# OpenEVSE_PLUS_v6_5_1.net
KiCad netlist of a schematic drawn in EAGLE
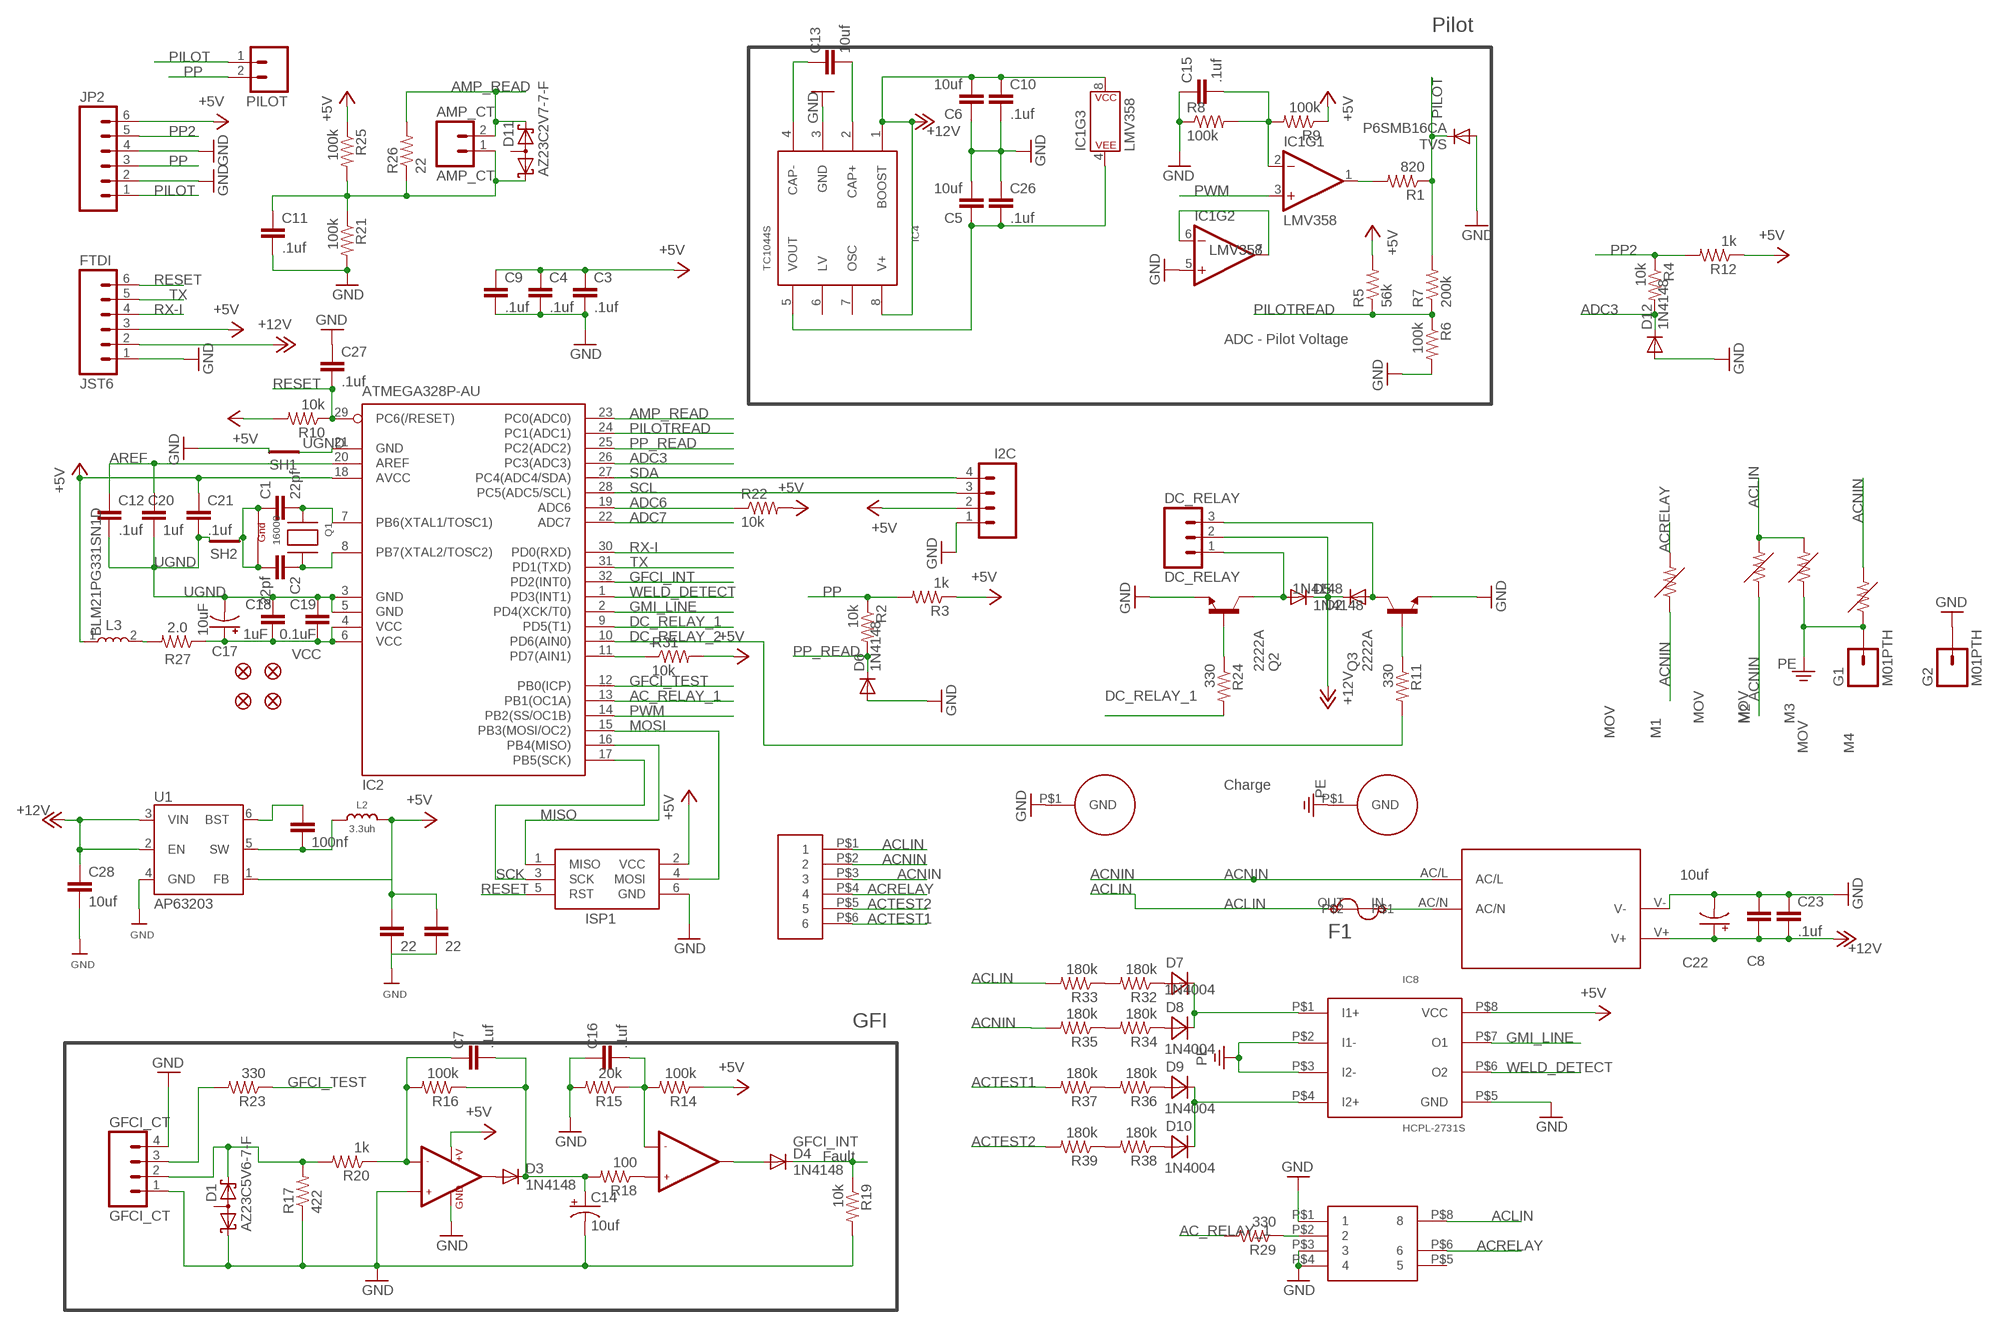
[diagram p0: schematic, sheet 1]

(export (version "E")
  (design (tool "Eeschema 10.0.6"))
  (components
    (comp (ref "AC")
      (value "JST-VH-6")
      (footprint "eagle-import:JST-VH-6")
      (libsource (lib "eagle-import") (part "JST-VH-6"))
    )
    (comp (ref "AMP_CT")
      (value "AMP_CT")
      (footprint "eagle-import:MOLEX_2")
      (libsource (lib "eagle-import") (part "MOLEX_2"))
    )
    (comp (ref "C1")
      (value "22pf")
      (footprint "eagle-import:0805")
      (libsource (lib "eagle-import") (part "CAP0805"))
    )
    (comp (ref "C2")
      (value "22pf")
      (footprint "eagle-import:0805")
      (libsource (lib "eagle-import") (part "CAP0805"))
    )
    (comp (ref "C3")
      (value ".1uf")
      (footprint "eagle-import:0805")
      (libsource (lib "eagle-import") (part "CAP0805"))
    )
    (comp (ref "C4")
      (value ".1uf")
      (footprint "eagle-import:0805")
      (libsource (lib "eagle-import") (part "CAP0805"))
    )
    (comp (ref "C5")
      (value "10uf")
      (footprint "eagle-import:0805")
      (libsource (lib "eagle-import") (part "CAP0805"))
    )
    (comp (ref "C6")
      (value "10uf")
      (footprint "eagle-import:0805")
      (libsource (lib "eagle-import") (part "CAP0805"))
    )
    (comp (ref "C7")
      (value ".1uf")
      (footprint "eagle-import:0805")
      (libsource (lib "eagle-import") (part "CAP0805"))
    )
    (comp (ref "C8")
      (value "1uf")
      (footprint "eagle-import:0805")
      (libsource (lib "eagle-import") (part "CAP0805"))
    )
    (comp (ref "C9")
      (value ".1uf")
      (footprint "eagle-import:0805")
      (libsource (lib "eagle-import") (part "CAP0805"))
    )
    (comp (ref "C10")
      (value ".1uf")
      (footprint "eagle-import:0805")
      (libsource (lib "eagle-import") (part "CAP0805"))
    )
    (comp (ref "C11")
      (value ".1uf")
      (footprint "eagle-import:0805")
      (libsource (lib "eagle-import") (part "CAP0805"))
    )
    (comp (ref "C12")
      (value ".1uf")
      (footprint "eagle-import:0805")
      (libsource (lib "eagle-import") (part "CAP0805"))
    )
    (comp (ref "C13")
      (value "10uf")
      (footprint "eagle-import:0805")
      (libsource (lib "eagle-import") (part "CAP0805"))
    )
    (comp (ref "C14")
      (value "10uf")
      (footprint "eagle-import:EIA3216")
      (libsource (lib "eagle-import") (part "CAP_POL1206"))
    )
    (comp (ref "C15")
      (value ".1uf")
      (footprint "eagle-import:0805")
      (libsource (lib "eagle-import") (part "CAP0805"))
    )
    (comp (ref "C16")
      (value ".1uf")
      (footprint "eagle-import:0805")
      (libsource (lib "eagle-import") (part "CAP0805"))
    )
    (comp (ref "C17")
      (value "10uF")
      (footprint "eagle-import:0603-POLAR")
      (libsource (lib "eagle-import") (part "10UF-POLAR-0603-6.3V-20%(TANT)"))
    )
    (comp (ref "C18")
      (value "1uF")
      (footprint "eagle-import:0805")
      (libsource (lib "eagle-import") (part "CAP0805"))
    )
    (comp (ref "C19")
      (value "0.1uF")
      (footprint "eagle-import:0805")
      (libsource (lib "eagle-import") (part "CAP0805"))
    )
    (comp (ref "C20")
      (value "1uf")
      (footprint "eagle-import:0805")
      (libsource (lib "eagle-import") (part "CAP0805"))
    )
    (comp (ref "C21")
      (value ".1uf")
      (footprint "eagle-import:0805")
      (libsource (lib "eagle-import") (part "CAP0805"))
    )
    (comp (ref "C22")
      (value "10uf")
      (footprint "eagle-import:EIA3216")
      (libsource (lib "eagle-import") (part "CAP_POL1206"))
    )
    (comp (ref "C23")
      (value ".1uf")
      (footprint "eagle-import:0805")
      (libsource (lib "eagle-import") (part "CAP0805"))
    )
    (comp (ref "C26")
      (value ".1uf")
      (footprint "eagle-import:0805")
      (libsource (lib "eagle-import") (part "CAP0805"))
    )
    (comp (ref "C27")
      (value ".1uf")
      (footprint "eagle-import:0805")
      (libsource (lib "eagle-import") (part "CAP0805"))
    )
    (comp (ref "C28")
      (value "10uf")
      (footprint "eagle-import:0805")
      (libsource (lib "eagle-import") (part "1.0UF-0805-25V-(+80/-20%)"))
    )
    (comp (ref "C29")
      (value "22")
      (footprint "eagle-import:0805")
      (libsource (lib "eagle-import") (part "1.0UF-0805-25V-(+80/-20%)"))
    )
    (comp (ref "C32")
      (value "100nf")
      (footprint "eagle-import:0805")
      (libsource (lib "eagle-import") (part "1.0UF-0805-25V-(+80/-20%)"))
    )
    (comp (ref "C33")
      (value "22")
      (footprint "eagle-import:0805")
      (libsource (lib "eagle-import") (part "1.0UF-0805-25V-(+80/-20%)"))
    )
    (comp (ref "D1")
      (value "AZ23C5V6-7-F")
      (footprint "eagle-import:SOT23")
      (libsource (lib "eagle-import") (part "BAS40-06"))
    )
    (comp (ref "D2")
      (value "1N4148")
      (footprint "eagle-import:SOD123")
      (libsource (lib "eagle-import") (part "DIODE-SOD123"))
    )
    (comp (ref "D3")
      (value "1N4148")
      (footprint "eagle-import:SOD123")
      (libsource (lib "eagle-import") (part "DIODE-SOD123"))
    )
    (comp (ref "D4")
      (value "1N4148")
      (footprint "eagle-import:SOD123")
      (libsource (lib "eagle-import") (part "DIODE-SOD123"))
    )
    (comp (ref "D5")
      (value "1N4148")
      (footprint "eagle-import:SOD123")
      (libsource (lib "eagle-import") (part "DIODE-SOD123"))
    )
    (comp (ref "D6")
      (value "1N4148")
      (footprint "eagle-import:SOD123")
      (libsource (lib "eagle-import") (part "DIODE-SOD123"))
    )
    (comp (ref "D7")
      (value "1N4004")
      (footprint "eagle-import:SMA")
      (libsource (lib "eagle-import") (part "MBRA340T3"))
    )
    (comp (ref "D8")
      (value "1N4004")
      (footprint "eagle-import:SMA")
      (libsource (lib "eagle-import") (part "MBRA340T3"))
    )
    (comp (ref "D9")
      (value "1N4004")
      (footprint "eagle-import:SMA")
      (libsource (lib "eagle-import") (part "MBRA340T3"))
    )
    (comp (ref "D10")
      (value "1N4004")
      (footprint "eagle-import:SMA")
      (libsource (lib "eagle-import") (part "MBRA340T3"))
    )
    (comp (ref "D11")
      (value "AZ23C2V7-7-F")
      (footprint "eagle-import:SOT23")
      (libsource (lib "eagle-import") (part "BAS40-06"))
    )
    (comp (ref "D12")
      (value "1N4148")
      (footprint "eagle-import:SOD123")
      (libsource (lib "eagle-import") (part "DIODE-SOD123"))
    )
    (comp (ref "DC_RELAY")
      (value "DC_RELAY")
      (footprint "eagle-import:MOLEX_3")
      (libsource (lib "eagle-import") (part "MOLEX_3"))
    )
    (comp (ref "F1")
      (value "BEL1.6AFUSE")
      (footprint "eagle-import:BELFUSE1A")
      (libsource (lib "eagle-import") (part "BEL1AFUSE"))
    )
    (comp (ref "FID1")
      (value "FIDUCIAL1X2.5")
      (footprint "eagle-import:FIDUCIAL-1X2.5")
      (libsource (lib "eagle-import") (part "FIDUCIAL1X2.5"))
    )
    (comp (ref "FID2")
      (value "FIDUCIAL1X2.5")
      (footprint "eagle-import:FIDUCIAL-1X2.5")
      (libsource (lib "eagle-import") (part "FIDUCIAL1X2.5"))
    )
    (comp (ref "FID3")
      (value "FIDUCIAL1X2.5")
      (footprint "eagle-import:FIDUCIAL-1X2.5")
      (libsource (lib "eagle-import") (part "FIDUCIAL1X2.5"))
    )
    (comp (ref "FID4")
      (value "FIDUCIAL1X2.5")
      (footprint "eagle-import:FIDUCIAL-1X2.5")
      (libsource (lib "eagle-import") (part "FIDUCIAL1X2.5"))
    )
    (comp (ref "FTDI")
      (value "JST6")
      (footprint "eagle-import:JST6")
      (libsource (lib "eagle-import") (part "JST6"))
    )
    (comp (ref "G1")
      (value "M01PTH")
      (footprint "eagle-import:1X01")
      (libsource (lib "eagle-import") (part "M01PTH"))
    )
    (comp (ref "G2")
      (value "M01PTH")
      (footprint "eagle-import:1X01")
      (libsource (lib "eagle-import") (part "M01PTH"))
    )
    (comp (ref "GFCI_CT")
      (value "GFCI_CT")
      (footprint "eagle-import:GFCI_4")
      (libsource (lib "eagle-import") (part "GFCI_4"))
    )
    (comp (ref "I2C")
      (value "M04JST-PTH-VERT")
      (footprint "eagle-import:JST-4-PTH-VERT")
      (libsource (lib "eagle-import") (part "M04JST-PTH-VERT"))
    )
    (comp (ref "IC1")
      (value "LMV358")
      (footprint "eagle-import:SO08")
      (libsource (lib "eagle-import") (part "LMV358SOIC"))
    )
    (comp (ref "IC2")
      (value "ATMEGA328P-AU")
      (footprint "eagle-import:TQFP32-08")
      (fields (field (name "MPN") "ATMEGA8-16AU"))
      (libsource (lib "eagle-import") (part "MEGA8-AI"))
    )
    (comp (ref "IC3")
      (value "LM358")
      (footprint "eagle-import:SO08")
      (libsource (lib "eagle-import") (part "LMV358"))
    )
    (comp (ref "IC4")
      (value "TC1044S")
      (footprint "eagle-import:SO-8")
      (libsource (lib "eagle-import") (part "TC1044S"))
    )
    (comp (ref "IC7")
      (value "AQH2223")
      (footprint "eagle-import:SIL8")
      (libsource (lib "eagle-import") (part "AQH2223"))
    )
    (comp (ref "IC8")
      (value "HCPL-2731S")
      (footprint "eagle-import:SIL8-2")
      (libsource (lib "eagle-import") (part "HCPL-2731S"))
    )
    (comp (ref "ISP1")
      (value "ISP1")
      (footprint "eagle-import:AVRISP")
      (libsource (lib "eagle-import") (part "AVRISP-6"))
    )
    (comp (ref "JP2")
      (value "M06POLAR_LOCK")
      (footprint "eagle-import:MOLEX-1X6_LOCK")
      (libsource (lib "eagle-import") (part "M06POLAR_LOCK"))
    )
    (comp (ref "L2")
      (value "3.3uh")
      (footprint "eagle-import:MICROBUILDER_INDUCTOR_5X5MM_NR5040_NOTHERMALS")
      (libsource (lib "eagle-import") (part "MICROBUILDER_INDUCTORNR5040"))
    )
    (comp (ref "L3")
      (value "BLM21PG331SN1D")
      (footprint "eagle-import:INDC2012X87")
      (fields (field (name "MF") "Murata"))
      (libsource (lib "eagle-import") (part "BLM21PG331SN1D"))
    )
    (comp (ref "M1")
      (value "MOV")
      (footprint "eagle-import:MOV")
      (libsource (lib "eagle-import") (part "MOV"))
    )
    (comp (ref "M2")
      (value "MOV")
      (footprint "eagle-import:MOV")
      (libsource (lib "eagle-import") (part "MOV"))
    )
    (comp (ref "M3")
      (value "MOV")
      (footprint "eagle-import:MOV")
      (libsource (lib "eagle-import") (part "MOV"))
    )
    (comp (ref "M4")
      (value "MOV")
      (footprint "eagle-import:MOV")
      (libsource (lib "eagle-import") (part "MOV"))
    )
    (comp (ref "PILOT")
      (value "M025MM")
      (footprint "eagle-import:SCREWTERMINAL-5MM-2")
      (libsource (lib "eagle-import") (part "M025MM"))
    )
    (comp (ref "PS1")
      (value "IRM-10-5")
      (footprint "eagle-import:IRM-10-5")
      (libsource (lib "eagle-import") (part "IRM-10-5"))
    )
    (comp (ref "Q1")
      (value "16000")
      (footprint "eagle-import:NX3225")
      (libsource (lib "eagle-import") (part "XTAL-4-3225"))
    )
    (comp (ref "Q2")
      (value "2222A")
      (footprint "eagle-import:SOT23")
      (libsource (lib "eagle-import") (part "BCX70SMD"))
    )
    (comp (ref "Q3")
      (value "2222A")
      (footprint "eagle-import:SOT23")
      (libsource (lib "eagle-import") (part "BCX70SMD"))
    )
    (comp (ref "R1")
      (value "820")
      (footprint "eagle-import:0805")
      (libsource (lib "eagle-import") (part "RESISTOR0805-RES"))
    )
    (comp (ref "R2")
      (value "10k")
      (footprint "eagle-import:0805")
      (libsource (lib "eagle-import") (part "RESISTOR0805-RES"))
    )
    (comp (ref "R3")
      (value "1k")
      (footprint "eagle-import:0805")
      (libsource (lib "eagle-import") (part "RESISTOR0805-RES"))
    )
    (comp (ref "R4")
      (value "10k")
      (footprint "eagle-import:0805")
      (libsource (lib "eagle-import") (part "RESISTOR0805-RES"))
    )
    (comp (ref "R5")
      (value "56k")
      (footprint "eagle-import:0805")
      (libsource (lib "eagle-import") (part "RESISTOR0805-RES"))
    )
    (comp (ref "R6")
      (value "100k")
      (footprint "eagle-import:0805")
      (libsource (lib "eagle-import") (part "RESISTOR0805-RES"))
    )
    (comp (ref "R7")
      (value "200k")
      (footprint "eagle-import:0805")
      (libsource (lib "eagle-import") (part "RESISTOR0805-RES"))
    )
    (comp (ref "R8")
      (value "100k")
      (footprint "eagle-import:0805")
      (libsource (lib "eagle-import") (part "RESISTOR0805-RES"))
    )
    (comp (ref "R9")
      (value "100k")
      (footprint "eagle-import:0805")
      (libsource (lib "eagle-import") (part "RESISTOR0805-RES"))
    )
    (comp (ref "R10")
      (value "10k")
      (footprint "eagle-import:0805")
      (libsource (lib "eagle-import") (part "RESISTOR0805-RES"))
    )
    (comp (ref "R11")
      (value "330")
      (footprint "eagle-import:0805")
      (libsource (lib "eagle-import") (part "RESISTOR0805-RES"))
    )
    (comp (ref "R12")
      (value "1k")
      (footprint "eagle-import:0805")
      (libsource (lib "eagle-import") (part "RESISTOR0805-RES"))
    )
    (comp (ref "R14")
      (value "100k")
      (footprint "eagle-import:0805")
      (libsource (lib "eagle-import") (part "RESISTOR0805-RES"))
    )
    (comp (ref "R15")
      (value "20k")
      (footprint "eagle-import:0805")
      (libsource (lib "eagle-import") (part "RESISTOR0805-RES"))
    )
    (comp (ref "R16")
      (value "100k")
      (footprint "eagle-import:0805")
      (libsource (lib "eagle-import") (part "RESISTOR0805-RES"))
    )
    (comp (ref "R17")
      (value "422")
      (footprint "eagle-import:0805")
      (libsource (lib "eagle-import") (part "RESISTOR0805-RES"))
    )
    (comp (ref "R18")
      (value "100")
      (footprint "eagle-import:0805")
      (libsource (lib "eagle-import") (part "RESISTOR0805-RES"))
    )
    (comp (ref "R19")
      (value "10k")
      (footprint "eagle-import:0805")
      (libsource (lib "eagle-import") (part "RESISTOR0805-RES"))
    )
    (comp (ref "R20")
      (value "1k")
      (footprint "eagle-import:0805")
      (libsource (lib "eagle-import") (part "RESISTOR0805-RES"))
    )
    (comp (ref "R21")
      (value "100k")
      (footprint "eagle-import:0805")
      (libsource (lib "eagle-import") (part "RESISTOR0805-RES"))
    )
    (comp (ref "R22")
      (value "10k")
      (footprint "eagle-import:0805")
      (libsource (lib "eagle-import") (part "RESISTOR0805-RES"))
    )
    (comp (ref "R23")
      (value "330")
      (footprint "eagle-import:0805")
      (libsource (lib "eagle-import") (part "RESISTOR0805-RES"))
    )
    (comp (ref "R24")
      (value "330")
      (footprint "eagle-import:0805")
      (libsource (lib "eagle-import") (part "RESISTOR0805-RES"))
    )
    (comp (ref "R25")
      (value "100k")
      (footprint "eagle-import:0805")
      (libsource (lib "eagle-import") (part "RESISTOR0805-RES"))
    )
    (comp (ref "R26")
      (value "22")
      (footprint "eagle-import:R1206")
      (libsource (lib "eagle-import") (part "R-US_R1206"))
    )
    (comp (ref "R27")
      (value "2.0")
      (footprint "eagle-import:0805")
      (libsource (lib "eagle-import") (part "RESISTOR0805-RES"))
    )
    (comp (ref "R29")
      (value "330")
      (footprint "eagle-import:0805")
      (libsource (lib "eagle-import") (part "RESISTOR0805-RES"))
    )
    (comp (ref "R31")
      (value "10k")
      (footprint "eagle-import:0805")
      (libsource (lib "eagle-import") (part "RESISTOR0805-RES"))
    )
    (comp (ref "R32")
      (value "180k")
      (footprint "eagle-import:1210")
      (libsource (lib "eagle-import") (part "0.1OHM-1/2W-1%(1210)"))
    )
    (comp (ref "R33")
      (value "180k")
      (footprint "eagle-import:1210")
      (libsource (lib "eagle-import") (part "0.1OHM-1/2W-1%(1210)"))
    )
    (comp (ref "R34")
      (value "180k")
      (footprint "eagle-import:1210")
      (libsource (lib "eagle-import") (part "0.1OHM-1/2W-1%(1210)"))
    )
    (comp (ref "R35")
      (value "180k")
      (footprint "eagle-import:1210")
      (libsource (lib "eagle-import") (part "0.1OHM-1/2W-1%(1210)"))
    )
    (comp (ref "R36")
      (value "180k")
      (footprint "eagle-import:1210")
      (libsource (lib "eagle-import") (part "0.1OHM-1/2W-1%(1210)"))
    )
    (comp (ref "R37")
      (value "180k")
      (footprint "eagle-import:1210")
      (libsource (lib "eagle-import") (part "0.1OHM-1/2W-1%(1210)"))
    )
    (comp (ref "R38")
      (value "180k")
      (footprint "eagle-import:1210")
      (libsource (lib "eagle-import") (part "0.1OHM-1/2W-1%(1210)"))
    )
    (comp (ref "R39")
      (value "180k")
      (footprint "eagle-import:1210")
      (libsource (lib "eagle-import") (part "0.1OHM-1/2W-1%(1210)"))
    )
    (comp (ref "SH1")
      (value "SHORT-HT5")
      (footprint "eagle-import:SHORT_TOP-50")
      (libsource (lib "eagle-import") (part "SHORT-HT5"))
    )
    (comp (ref "SH2")
      (value "SHORT-HT5")
      (footprint "eagle-import:SHORT_TOP-50")
      (libsource (lib "eagle-import") (part "SHORT-HT5"))
    )
    (comp (ref "TVS")
      (value "P6SMB16CA")
      (footprint "eagle-import:SMB")
      (libsource (lib "eagle-import") (part "DIODE-SMB"))
    )
    (comp (ref "U$3")
      (value "HOLE")
      (footprint "eagle-import:HOLE")
      (libsource (lib "eagle-import") (part "HOLE"))
    )
    (comp (ref "U$9")
      (value "HOLE")
      (footprint "eagle-import:HOLE")
      (libsource (lib "eagle-import") (part "HOLE"))
    )
    (comp (ref "U1")
      (value "AP63203")
      (footprint "eagle-import:SOT23-6")
      (libsource (lib "eagle-import") (part "AP63203"))
    )
  )
  (nets
    (net (code "1") (name "+5V") (class "Default")
      (node (ref "C21") (pin "1") (pinfunction "1_1") (pintype "passive"))
      (node (ref "C29") (pin "1") (pinfunction "1_1") (pintype "passive"))
      (node (ref "C3") (pin "1") (pinfunction "1_1") (pintype "passive"))
      (node (ref "C33") (pin "1") (pinfunction "1_1") (pintype "passive"))
      (node (ref "C4") (pin "1") (pinfunction "1_1") (pintype "passive"))
      (node (ref "C9") (pin "1") (pinfunction "1_1") (pintype "passive"))
      (node (ref "FTDI") (pin "3") (pinfunction "3_3") (pintype "passive"))
      (node (ref "I2C") (pin "2") (pinfunction "2_2") (pintype "passive"))
      (node (ref "IC2") (pin "18") (pinfunction "AVCC_18") (pintype "power_in"))
      (node (ref "IC3") (pin "8") (pinfunction "+V_8") (pintype "power_in"))
      (node (ref "IC8") (pin "P$8") (pinfunction "VCC_P$8") (pintype "bidirectional"))
      (node (ref "ISP1") (pin "2") (pinfunction "VCC_2") (pintype "power_in"))
      (node (ref "JP2") (pin "6") (pinfunction "6_6") (pintype "passive"))
      (node (ref "L2") (pin "P$2") (pinfunction "2_P$2") (pintype "passive"))
      (node (ref "L3") (pin "1") (pinfunction "1_1") (pintype "passive"))
      (node (ref "R10") (pin "2") (pinfunction "2_2") (pintype "passive"))
      (node (ref "R12") (pin "1") (pinfunction "1_1") (pintype "passive"))
      (node (ref "R14") (pin "1") (pinfunction "1_1") (pintype "passive"))
      (node (ref "R22") (pin "2") (pinfunction "2_2") (pintype "passive"))
      (node (ref "R25") (pin "1") (pinfunction "1_1") (pintype "passive"))
      (node (ref "R3") (pin "1") (pinfunction "1_1") (pintype "passive"))
      (node (ref "R31") (pin "2") (pinfunction "2_2") (pintype "passive"))
      (node (ref "R5") (pin "2") (pinfunction "2_2") (pintype "passive"))
      (node (ref "R9") (pin "1") (pinfunction "1_1") (pintype "passive"))
      (node (ref "U1") (pin "1") (pinfunction "FB_1") (pintype "bidirectional"))
    )
    (net (code "2") (name "+12V") (class "Default")
      (node (ref "C10") (pin "1") (pinfunction "1_1") (pintype "passive"))
      (node (ref "C22") (pin "A") (pinfunction "+_A") (pintype "passive"))
      (node (ref "C23") (pin "2") (pinfunction "2_2") (pintype "passive"))
      (node (ref "C28") (pin "1") (pinfunction "1_1") (pintype "passive"))
      (node (ref "C6") (pin "2") (pinfunction "2_2") (pintype "passive"))
      (node (ref "C8") (pin "1") (pinfunction "1_1") (pintype "passive"))
      (node (ref "D2") (pin "C") (pinfunction "C_C") (pintype "passive"))
      (node (ref "D5") (pin "C") (pinfunction "C_C") (pintype "passive"))
      (node (ref "DC_RELAY") (pin "2") (pinfunction "2_2") (pintype "passive"))
      (node (ref "FTDI") (pin "2") (pinfunction "2_2") (pintype "passive"))
      (node (ref "IC1") (pin "8") (pinfunction "P$V+_8") (pintype "bidirectional"))
      (node (ref "IC4") (pin "1") (pinfunction "BOOST_1") (pintype "bidirectional"))
      (node (ref "IC4") (pin "8") (pinfunction "V+_8") (pintype "bidirectional"))
      (node (ref "PS1") (pin "V+") (pinfunction "V+_V+") (pintype "bidirectional"))
      (node (ref "U1") (pin "2") (pinfunction "EN_2") (pintype "bidirectional"))
      (node (ref "U1") (pin "3") (pinfunction "VIN_3") (pintype "bidirectional"))
    )
    (net (code "3") (name "/ACLIN") (class "Default")
      (node (ref "AC") (pin "P$1") (pinfunction "1_P$1") (pintype "bidirectional"))
      (node (ref "F1") (pin "OUT") (pinfunction "P$1_OUT") (pintype "bidirectional"))
      (node (ref "IC7") (pin "P$8") (pinfunction "8_P$8") (pintype "bidirectional"))
      (node (ref "M2") (pin "P$2") (pinfunction "2_P$2") (pintype "passive"))
      (node (ref "M3") (pin "P$2") (pinfunction "2_P$2") (pintype "passive"))
      (node (ref "R33") (pin "2") (pinfunction "2_2") (pintype "passive"))
    )
    (net (code "4") (name "/ACNIN") (class "Default")
      (node (ref "AC") (pin "P$2") (pinfunction "2_P$2") (pintype "bidirectional"))
      (node (ref "AC") (pin "P$3") (pinfunction "3_P$3") (pintype "bidirectional"))
      (node (ref "M1") (pin "P$1") (pinfunction "1_P$1") (pintype "passive"))
      (node (ref "M2") (pin "P$1") (pinfunction "1_P$1") (pintype "passive"))
      (node (ref "M4") (pin "P$2") (pinfunction "2_P$2") (pintype "passive"))
      (node (ref "PS1") (pin "AC/L") (pinfunction "AC/L_AC/L") (pintype "bidirectional"))
      (node (ref "R35") (pin "2") (pinfunction "2_2") (pintype "passive"))
    )
    (net (code "5") (name "/ACRELAY") (class "Default")
      (node (ref "AC") (pin "P$4") (pinfunction "4_P$4") (pintype "bidirectional"))
      (node (ref "IC7") (pin "P$6") (pinfunction "6_P$6") (pintype "bidirectional"))
      (node (ref "M1") (pin "P$2") (pinfunction "2_P$2") (pintype "passive"))
    )
    (net (code "6") (name "/ACTEST1") (class "Default")
      (node (ref "AC") (pin "P$6") (pinfunction "6_P$6") (pintype "bidirectional"))
      (node (ref "R37") (pin "2") (pinfunction "2_2") (pintype "passive"))
    )
    (net (code "7") (name "/ACTEST2") (class "Default")
      (node (ref "AC") (pin "P$5") (pinfunction "5_P$5") (pintype "bidirectional"))
      (node (ref "R39") (pin "2") (pinfunction "2_2") (pintype "passive"))
    )
    (net (code "8") (name "/AC_RELAY_1") (class "Default")
      (node (ref "IC2") (pin "13") (pinfunction "PB1(OC1A)_13") (pintype "bidirectional"))
      (node (ref "R29") (pin "2") (pinfunction "2_2") (pintype "passive"))
    )
    (net (code "9") (name "/ADC3") (class "Default")
      (node (ref "D12") (pin "C") (pinfunction "C_C") (pintype "passive"))
      (node (ref "IC2") (pin "26") (pinfunction "PC3(ADC3)_26") (pintype "bidirectional"))
      (node (ref "R4") (pin "2") (pinfunction "2_2") (pintype "passive"))
    )
    (net (code "10") (name "/ADC6") (class "Default")
      (node (ref "IC2") (pin "19") (pinfunction "ADC6_19") (pintype "bidirectional"))
      (node (ref "R22") (pin "1") (pinfunction "1_1") (pintype "passive"))
    )
    (net (code "11") (name "/ADC7") (class "Default")
      (node (ref "IC2") (pin "22") (pinfunction "ADC7_22") (pintype "bidirectional"))
    )
    (net (code "12") (name "/AMP_READ") (class "Default")
      (node (ref "AMP_CT") (pin "2") (pinfunction "2_2") (pintype "passive"))
      (node (ref "D11") (pin "2") (pinfunction "K2_2") (pintype "passive"))
      (node (ref "IC2") (pin "23") (pinfunction "PC0(ADC0)_23") (pintype "bidirectional"))
      (node (ref "R26") (pin "2") (pinfunction "2_2") (pintype "passive"))
    )
    (net (code "13") (name "/AREF") (class "Default")
      (node (ref "C12") (pin "1") (pinfunction "1_1") (pintype "passive"))
      (node (ref "C20") (pin "1") (pinfunction "1_1") (pintype "passive"))
      (node (ref "IC2") (pin "20") (pinfunction "AREF_20") (pintype "passive"))
    )
    (net (code "14") (name "/DC_RELAY_1") (class "Default")
      (node (ref "IC2") (pin "9") (pinfunction "PD5(T1)_9") (pintype "bidirectional"))
      (node (ref "R24") (pin "2") (pinfunction "2_2") (pintype "passive"))
    )
    (net (code "15") (name "/DC_RELAY_2") (class "Default")
      (node (ref "IC2") (pin "10") (pinfunction "PD6(AIN0)_10") (pintype "bidirectional"))
      (node (ref "R11") (pin "2") (pinfunction "2_2") (pintype "passive"))
    )
    (net (code "16") (name "/GFCI_INT") (class "Default")
      (node (ref "D4") (pin "C") (pinfunction "C_C") (pintype "passive"))
      (node (ref "IC2") (pin "32") (pinfunction "PD2(INT0)_32") (pintype "bidirectional"))
      (node (ref "R19") (pin "1") (pinfunction "1_1") (pintype "passive"))
    )
    (net (code "17") (name "/GFCI_TEST") (class "Default")
      (node (ref "IC2") (pin "12") (pinfunction "PB0(ICP)_12") (pintype "bidirectional"))
      (node (ref "R23") (pin "1") (pinfunction "1_1") (pintype "passive"))
    )
    (net (code "18") (name "/GMI_LINE") (class "Default")
      (node (ref "IC2") (pin "2") (pinfunction "PD4(XCK/T0)_2") (pintype "bidirectional"))
      (node (ref "IC8") (pin "P$7") (pinfunction "O1_P$7") (pintype "bidirectional"))
    )
    (net (code "19") (name "/MISO") (class "Default")
      (node (ref "IC2") (pin "16") (pinfunction "PB4(MISO)_16") (pintype "bidirectional"))
      (node (ref "ISP1") (pin "1") (pinfunction "MISO_1") (pintype "input"))
    )
    (net (code "20") (name "/MOSI") (class "Default")
      (node (ref "IC2") (pin "15") (pinfunction "PB3(MOSI/OC2)_15") (pintype "bidirectional"))
      (node (ref "ISP1") (pin "4") (pinfunction "MOSI_4") (pintype "output"))
    )
    (net (code "21") (name "/PILOT") (class "Default")
      (node (ref "JP2") (pin "1") (pinfunction "1_1") (pintype "passive"))
      (node (ref "PILOT") (pin "1") (pinfunction "1_1") (pintype "passive"))
      (node (ref "R1") (pin "1") (pinfunction "1_1") (pintype "passive"))
      (node (ref "R7") (pin "2") (pinfunction "2_2") (pintype "passive"))
      (node (ref "TVS") (pin "C") (pinfunction "C_C") (pintype "passive"))
    )
    (net (code "22") (name "/PILOTREAD") (class "Default")
      (node (ref "IC2") (pin "24") (pinfunction "PC1(ADC1)_24") (pintype "bidirectional"))
      (node (ref "R5") (pin "1") (pinfunction "1_1") (pintype "passive"))
      (node (ref "R6") (pin "1") (pinfunction "1_1") (pintype "passive"))
      (node (ref "R7") (pin "1") (pinfunction "1_1") (pintype "passive"))
    )
    (net (code "23") (name "/PP") (class "Default")
      (node (ref "JP2") (pin "3") (pinfunction "3_3") (pintype "passive"))
      (node (ref "PILOT") (pin "2") (pinfunction "2_2") (pintype "passive"))
      (node (ref "R2") (pin "1") (pinfunction "1_1") (pintype "passive"))
      (node (ref "R3") (pin "2") (pinfunction "2_2") (pintype "passive"))
    )
    (net (code "24") (name "/PP2") (class "Default")
      (node (ref "JP2") (pin "5") (pinfunction "5_5") (pintype "passive"))
      (node (ref "R12") (pin "2") (pinfunction "2_2") (pintype "passive"))
      (node (ref "R4") (pin "1") (pinfunction "1_1") (pintype "passive"))
    )
    (net (code "25") (name "/PP_READ") (class "Default")
      (node (ref "D6") (pin "C") (pinfunction "C_C") (pintype "passive"))
      (node (ref "IC2") (pin "25") (pinfunction "PC2(ADC2)_25") (pintype "bidirectional"))
      (node (ref "R2") (pin "2") (pinfunction "2_2") (pintype "passive"))
    )
    (net (code "26") (name "/PWM") (class "Default")
      (node (ref "IC1") (pin "3") (pinfunction "+IN_3") (pintype "input"))
      (node (ref "IC2") (pin "14") (pinfunction "PB2(SS/OC1B)_14") (pintype "bidirectional"))
    )
    (net (code "27") (name "/RESET") (class "Default")
      (node (ref "C27") (pin "2") (pinfunction "2_2") (pintype "passive"))
      (node (ref "FTDI") (pin "6") (pinfunction "6_6") (pintype "passive"))
      (node (ref "IC2") (pin "29") (pinfunction "PC6(/RESET)_29") (pintype "bidirectional"))
      (node (ref "ISP1") (pin "5") (pinfunction "RST_5") (pintype "output"))
      (node (ref "R10") (pin "1") (pinfunction "1_1") (pintype "passive"))
    )
    (net (code "28") (name "/RX-I") (class "Default")
      (node (ref "FTDI") (pin "4") (pinfunction "4_4") (pintype "passive"))
      (node (ref "IC2") (pin "30") (pinfunction "PD0(RXD)_30") (pintype "bidirectional"))
    )
    (net (code "29") (name "/SCK") (class "Default")
      (node (ref "IC2") (pin "17") (pinfunction "PB5(SCK)_17") (pintype "bidirectional"))
      (node (ref "ISP1") (pin "3") (pinfunction "SCK_3") (pintype "output"))
    )
    (net (code "30") (name "/SCL") (class "Default")
      (node (ref "I2C") (pin "3") (pinfunction "3_3") (pintype "passive"))
      (node (ref "IC2") (pin "28") (pinfunction "PC5(ADC5/SCL)_28") (pintype "bidirectional"))
    )
    (net (code "31") (name "/SDA") (class "Default")
      (node (ref "I2C") (pin "4") (pinfunction "4_4") (pintype "passive"))
      (node (ref "IC2") (pin "27") (pinfunction "PC4(ADC4/SDA)_27") (pintype "bidirectional"))
    )
    (net (code "32") (name "/TX") (class "Default")
      (node (ref "FTDI") (pin "5") (pinfunction "5_5") (pintype "passive"))
      (node (ref "IC2") (pin "31") (pinfunction "PD1(TXD)_31") (pintype "bidirectional"))
    )
    (net (code "33") (name "/UGND") (class "Default")
      (node (ref "C12") (pin "2") (pinfunction "2_2") (pintype "passive"))
      (node (ref "C17") (pin "-") (pinfunction "-_-") (pintype "passive"))
      (node (ref "C18") (pin "1") (pinfunction "1_1") (pintype "passive"))
      (node (ref "C19") (pin "1") (pinfunction "1_1") (pintype "passive"))
      (node (ref "C20") (pin "2") (pinfunction "2_2") (pintype "passive"))
      (node (ref "C21") (pin "2") (pinfunction "2_2") (pintype "passive"))
      (node (ref "IC2") (pin "21") (pinfunction "GND_21") (pintype "power_in"))
      (node (ref "IC2") (pin "3") (pinfunction "GND_3") (pintype "power_in"))
      (node (ref "IC2") (pin "5") (pinfunction "GND_5") (pintype "power_in"))
      (node (ref "SH1") (pin "1") (pinfunction "P$1_1") (pintype "bidirectional"))
      (node (ref "SH2") (pin "2") (pinfunction "P$2_2") (pintype "bidirectional"))
    )
    (net (code "34") (name "/VCC") (class "Default")
      (node (ref "C17") (pin "+") (pinfunction "+_+") (pintype "passive"))
      (node (ref "C18") (pin "2") (pinfunction "2_2") (pintype "passive"))
      (node (ref "C19") (pin "2") (pinfunction "2_2") (pintype "passive"))
      (node (ref "IC2") (pin "4") (pinfunction "VCC_4") (pintype "power_in"))
      (node (ref "IC2") (pin "6") (pinfunction "VCC_6") (pintype "power_in"))
      (node (ref "R27") (pin "1") (pinfunction "1_1") (pintype "passive"))
    )
    (net (code "35") (name "/WELD_DETECT") (class "Default")
      (node (ref "IC2") (pin "1") (pinfunction "PD3(INT1)_1") (pintype "bidirectional"))
      (node (ref "IC8") (pin "P$6") (pinfunction "O2_P$6") (pintype "bidirectional"))
    )
    (net (code "36") (name "GND") (class "Default")
      (node (ref "C10") (pin "2") (pinfunction "2_2") (pintype "passive"))
      (node (ref "C11") (pin "2") (pinfunction "2_2") (pintype "passive"))
      (node (ref "C14") (pin "C") (pinfunction "-_C") (pintype "passive"))
      (node (ref "C15") (pin "1") (pinfunction "1_1") (pintype "passive"))
      (node (ref "C16") (pin "1") (pinfunction "1_1") (pintype "passive"))
      (node (ref "C22") (pin "C") (pinfunction "-_C") (pintype "passive"))
      (node (ref "C23") (pin "1") (pinfunction "1_1") (pintype "passive"))
      (node (ref "C26") (pin "1") (pinfunction "1_1") (pintype "passive"))
      (node (ref "C27") (pin "1") (pinfunction "1_1") (pintype "passive"))
      (node (ref "C28") (pin "2") (pinfunction "2_2") (pintype "passive"))
      (node (ref "C29") (pin "2") (pinfunction "2_2") (pintype "passive"))
      (node (ref "C3") (pin "2") (pinfunction "2_2") (pintype "passive"))
      (node (ref "C33") (pin "2") (pinfunction "2_2") (pintype "passive"))
      (node (ref "C4") (pin "2") (pinfunction "2_2") (pintype "passive"))
      (node (ref "C5") (pin "2") (pinfunction "2_2") (pintype "passive"))
      (node (ref "C6") (pin "1") (pinfunction "1_1") (pintype "passive"))
      (node (ref "C8") (pin "2") (pinfunction "2_2") (pintype "passive"))
      (node (ref "C9") (pin "2") (pinfunction "2_2") (pintype "passive"))
      (node (ref "D1") (pin "1") (pinfunction "K1_1") (pintype "passive"))
      (node (ref "D12") (pin "A") (pinfunction "A_A") (pintype "passive"))
      (node (ref "D6") (pin "A") (pinfunction "A_A") (pintype "passive"))
      (node (ref "FTDI") (pin "1") (pinfunction "1_1") (pintype "passive"))
      (node (ref "G2") (pin "1") (pinfunction "1_1") (pintype "passive"))
      (node (ref "GFCI_CT") (pin "1") (pinfunction "1_1") (pintype "passive"))
      (node (ref "GFCI_CT") (pin "4") (pinfunction "4_4") (pintype "passive"))
      (node (ref "I2C") (pin "1") (pinfunction "1_1") (pintype "passive"))
      (node (ref "IC1") (pin "5") (pinfunction "+IN_5") (pintype "input"))
      (node (ref "IC3") (pin "3") (pinfunction "+IN1_3") (pintype "input"))
      (node (ref "IC3") (pin "4") (pinfunction "GND_4") (pintype "power_in"))
      (node (ref "IC4") (pin "3") (pinfunction "GND_3") (pintype "bidirectional"))
      (node (ref "IC7") (pin "P$1") (pinfunction "1_P$1") (pintype "bidirectional"))
      (node (ref "IC7") (pin "P$3") (pinfunction "3_P$3") (pintype "bidirectional"))
      (node (ref "IC7") (pin "P$4") (pinfunction "4_P$4") (pintype "bidirectional"))
      (node (ref "IC8") (pin "P$5") (pinfunction "GND_P$5") (pintype "bidirectional"))
      (node (ref "ISP1") (pin "6") (pinfunction "GND_6") (pintype "power_in"))
      (node (ref "JP2") (pin "2") (pinfunction "2_2") (pintype "passive"))
      (node (ref "JP2") (pin "4") (pinfunction "4_4") (pintype "passive"))
      (node (ref "PS1") (pin "V-") (pinfunction "V-_V-") (pintype "bidirectional"))
      (node (ref "Q2") (pin "2") (pinfunction "E_2") (pintype "passive"))
      (node (ref "Q3") (pin "2") (pinfunction "E_2") (pintype "passive"))
      (node (ref "R15") (pin "2") (pinfunction "2_2") (pintype "passive"))
      (node (ref "R17") (pin "1") (pinfunction "1_1") (pintype "passive"))
      (node (ref "R19") (pin "2") (pinfunction "2_2") (pintype "passive"))
      (node (ref "R21") (pin "2") (pinfunction "2_2") (pintype "passive"))
      (node (ref "R6") (pin "2") (pinfunction "2_2") (pintype "passive"))
      (node (ref "R8") (pin "1") (pinfunction "1_1") (pintype "passive"))
      (node (ref "SH1") (pin "2") (pinfunction "P$2_2") (pintype "bidirectional"))
      (node (ref "TVS") (pin "A") (pinfunction "A_A") (pintype "passive"))
      (node (ref "U$9") (pin "P$1") (pinfunction "GND_P$1") (pintype "bidirectional"))
      (node (ref "U1") (pin "4") (pinfunction "GND_4") (pintype "bidirectional"))
    )
    (net (code "37") (name "Net-(C14-+)") (class "Default")
      (node (ref "C14") (pin "A") (pinfunction "+_A") (pintype "passive"))
      (node (ref "C7") (pin "2") (pinfunction "2_2") (pintype "passive"))
      (node (ref "D3") (pin "C") (pinfunction "C_C") (pintype "passive"))
      (node (ref "R16") (pin "1") (pinfunction "1_1") (pintype "passive"))
      (node (ref "R18") (pin "2") (pinfunction "2_2") (pintype "passive"))
    )
    (net (code "38") (name "Net-(D1-K2)") (class "Default")
      (node (ref "D1") (pin "2") (pinfunction "K2_2") (pintype "passive"))
      (node (ref "GFCI_CT") (pin "2") (pinfunction "2_2") (pintype "passive"))
      (node (ref "R17") (pin "2") (pinfunction "2_2") (pintype "passive"))
      (node (ref "R20") (pin "2") (pinfunction "2_2") (pintype "passive"))
    )
    (net (code "39") (name "Net-(D7-PadA)") (class "Default")
      (node (ref "D7") (pin "A") (pinfunction "A_A") (pintype "passive"))
      (node (ref "R32") (pin "1") (pinfunction "1_1") (pintype "passive"))
    )
    (net (code "40") (name "Net-(D8-PadA)") (class "Default")
      (node (ref "D8") (pin "A") (pinfunction "A_A") (pintype "passive"))
      (node (ref "R34") (pin "1") (pinfunction "1_1") (pintype "passive"))
    )
    (net (code "41") (name "Net-(D9-PadA)") (class "Default")
      (node (ref "D9") (pin "A") (pinfunction "A_A") (pintype "passive"))
      (node (ref "R36") (pin "1") (pinfunction "1_1") (pintype "passive"))
    )
    (net (code "42") (name "Net-(D10-PadA)") (class "Default")
      (node (ref "D10") (pin "A") (pinfunction "A_A") (pintype "passive"))
      (node (ref "R38") (pin "1") (pinfunction "1_1") (pintype "passive"))
    )
    (net (code "43") (name "Net-(D11-K1)") (class "Default")
      (node (ref "AMP_CT") (pin "1") (pinfunction "1_1") (pintype "passive"))
      (node (ref "C11") (pin "1") (pinfunction "1_1") (pintype "passive"))
      (node (ref "D11") (pin "1") (pinfunction "K1_1") (pintype "passive"))
      (node (ref "R21") (pin "1") (pinfunction "1_1") (pintype "passive"))
      (node (ref "R25") (pin "2") (pinfunction "2_2") (pintype "passive"))
      (node (ref "R26") (pin "1") (pinfunction "1_1") (pintype "passive"))
    )
    (net (code "44") (name "Net-(F1-P$2)") (class "Default")
      (node (ref "F1") (pin "IN") (pinfunction "P$2_IN") (pintype "bidirectional"))
      (node (ref "PS1") (pin "AC/N") (pinfunction "AC/N_AC/N") (pintype "bidirectional"))
    )
    (net (code "45") (name "Net-(GFCI_CT-Pad3)") (class "Default")
      (node (ref "GFCI_CT") (pin "3") (pinfunction "3_3") (pintype "passive"))
      (node (ref "R23") (pin "2") (pinfunction "2_2") (pintype "passive"))
    )
    (net (code "46") (name "Net-(IC1A--IN)") (class "Default")
      (node (ref "C15") (pin "2") (pinfunction "2_2") (pintype "passive"))
      (node (ref "IC1") (pin "2") (pinfunction "-IN_2") (pintype "input"))
      (node (ref "R8") (pin "2") (pinfunction "2_2") (pintype "passive"))
      (node (ref "R9") (pin "2") (pinfunction "2_2") (pintype "passive"))
    )
    (net (code "47") (name "Net-(IC1A-OUT)") (class "Default")
      (node (ref "IC1") (pin "1") (pinfunction "OUT_1") (pintype "output"))
      (node (ref "R1") (pin "2") (pinfunction "2_2") (pintype "passive"))
    )
    (net (code "48") (name "Net-(IC1B--IN)") (class "Default")
      (node (ref "IC1") (pin "6") (pinfunction "-IN_6") (pintype "input"))
      (node (ref "IC1") (pin "7") (pinfunction "OUT_7") (pintype "output"))
    )
    (net (code "49") (name "Net-(IC1C-P$V-)") (class "Default")
      (node (ref "C26") (pin "2") (pinfunction "2_2") (pintype "passive"))
      (node (ref "C5") (pin "1") (pinfunction "1_1") (pintype "passive"))
      (node (ref "IC1") (pin "4") (pinfunction "P$V-_4") (pintype "bidirectional"))
      (node (ref "IC4") (pin "5") (pinfunction "VOUT_5") (pintype "bidirectional"))
    )
    (net (code "50") (name "Net-(IC2-PB6(XTAL1{slash}TOSC1))") (class "Default")
      (node (ref "C1") (pin "2") (pinfunction "2_2") (pintype "passive"))
      (node (ref "IC2") (pin "7") (pinfunction "PB6(XTAL1/TOSC1)_7") (pintype "bidirectional"))
      (node (ref "Q1") (pin "2") (pinfunction "X1_2") (pintype "bidirectional"))
    )
    (net (code "51") (name "Net-(IC2-PB7(XTAL2{slash}TOSC2))") (class "Default")
      (node (ref "C2") (pin "1") (pinfunction "1_1") (pintype "passive"))
      (node (ref "IC2") (pin "8") (pinfunction "PB7(XTAL2/TOSC2)_8") (pintype "bidirectional"))
      (node (ref "Q1") (pin "4") (pinfunction "X2_4") (pintype "bidirectional"))
    )
    (net (code "52") (name "Net-(IC2-PD7(AIN1))") (class "Default")
      (node (ref "IC2") (pin "11") (pinfunction "PD7(AIN1)_11") (pintype "bidirectional"))
      (node (ref "R31") (pin "1") (pinfunction "1_1") (pintype "passive"))
    )
    (net (code "53") (name "Net-(IC3A--IN1)") (class "Default")
      (node (ref "C7") (pin "1") (pinfunction "1_1") (pintype "passive"))
      (node (ref "IC3") (pin "2") (pinfunction "-IN1_2") (pintype "input"))
      (node (ref "R16") (pin "2") (pinfunction "2_2") (pintype "passive"))
      (node (ref "R20") (pin "1") (pinfunction "1_1") (pintype "passive"))
    )
    (net (code "54") (name "Net-(IC3A-OUT1)") (class "Default")
      (node (ref "D3") (pin "A") (pinfunction "A_A") (pintype "passive"))
      (node (ref "IC3") (pin "1") (pinfunction "OUT1_1") (pintype "output"))
    )
    (net (code "55") (name "Net-(IC3B-+IN2)") (class "Default")
      (node (ref "IC3") (pin "5") (pinfunction "+IN2_5") (pintype "input"))
      (node (ref "R18") (pin "1") (pinfunction "1_1") (pintype "passive"))
    )
    (net (code "56") (name "Net-(IC3B--IN2)") (class "Default")
      (node (ref "C16") (pin "2") (pinfunction "2_2") (pintype "passive"))
      (node (ref "IC3") (pin "6") (pinfunction "-IN2_6") (pintype "input"))
      (node (ref "R14") (pin "2") (pinfunction "2_2") (pintype "passive"))
      (node (ref "R15") (pin "1") (pinfunction "1_1") (pintype "passive"))
    )
    (net (code "57") (name "Net-(IC3B-OUT2)") (class "Default")
      (node (ref "D4") (pin "A") (pinfunction "A_A") (pintype "passive"))
      (node (ref "IC3") (pin "7") (pinfunction "OUT2_7") (pintype "output"))
    )
    (net (code "58") (name "Net-(IC4-CAP+)") (class "Default")
      (node (ref "C13") (pin "2") (pinfunction "2_2") (pintype "passive"))
      (node (ref "IC4") (pin "2") (pinfunction "CAP+_2") (pintype "bidirectional"))
    )
    (net (code "59") (name "Net-(IC4-CAP-)") (class "Default")
      (node (ref "C13") (pin "1") (pinfunction "1_1") (pintype "passive"))
      (node (ref "IC4") (pin "4") (pinfunction "CAP-_4") (pintype "bidirectional"))
    )
    (net (code "60") (name "Net-(IC7-2)") (class "Default")
      (node (ref "IC7") (pin "P$2") (pinfunction "2_P$2") (pintype "bidirectional"))
      (node (ref "R29") (pin "1") (pinfunction "1_1") (pintype "passive"))
    )
    (net (code "61") (name "Net-(IC8-I1+)") (class "Default")
      (node (ref "D7") (pin "C") (pinfunction "C_C") (pintype "passive"))
      (node (ref "D8") (pin "C") (pinfunction "C_C") (pintype "passive"))
      (node (ref "IC8") (pin "P$1") (pinfunction "I1+_P$1") (pintype "bidirectional"))
    )
    (net (code "62") (name "Net-(IC8-I2+)") (class "Default")
      (node (ref "D10") (pin "C") (pinfunction "C_C") (pintype "passive"))
      (node (ref "D9") (pin "C") (pinfunction "C_C") (pintype "passive"))
      (node (ref "IC8") (pin "P$4") (pinfunction "I2+_P$4") (pintype "bidirectional"))
    )
    (net (code "63") (name "Net-(L2-1)") (class "Default")
      (node (ref "C32") (pin "2") (pinfunction "2_2") (pintype "passive"))
      (node (ref "L2") (pin "P$1") (pinfunction "1_P$1") (pintype "passive"))
      (node (ref "U1") (pin "5") (pinfunction "SW_5") (pintype "bidirectional"))
    )
    (net (code "64") (name "Net-(L3-Pad2)") (class "Default")
      (node (ref "L3") (pin "2") (pinfunction "2_2") (pintype "passive"))
      (node (ref "R27") (pin "2") (pinfunction "2_2") (pintype "passive"))
    )
    (net (code "65") (name "Net-(Q1-G1)") (class "Default")
      (node (ref "C1") (pin "1") (pinfunction "1_1") (pintype "passive"))
      (node (ref "C2") (pin "2") (pinfunction "2_2") (pintype "passive"))
      (node (ref "Q1") (pin "1") (pinfunction "G1_1") (pintype "power_in"))
      (node (ref "Q1") (pin "3") (pinfunction "G2_3") (pintype "power_in"))
      (node (ref "SH2") (pin "1") (pinfunction "P$1_1") (pintype "bidirectional"))
    )
    (net (code "66") (name "Net-(Q2-B)") (class "Default")
      (node (ref "Q2") (pin "1") (pinfunction "B_1") (pintype "passive"))
      (node (ref "R24") (pin "1") (pinfunction "1_1") (pintype "passive"))
    )
    (net (code "67") (name "Net-(Q2-C)") (class "Default")
      (node (ref "D5") (pin "A") (pinfunction "A_A") (pintype "passive"))
      (node (ref "DC_RELAY") (pin "1") (pinfunction "1_1") (pintype "passive"))
      (node (ref "Q2") (pin "3") (pinfunction "C_3") (pintype "passive"))
    )
    (net (code "68") (name "Net-(Q3-B)") (class "Default")
      (node (ref "Q3") (pin "1") (pinfunction "B_1") (pintype "passive"))
      (node (ref "R11") (pin "1") (pinfunction "1_1") (pintype "passive"))
    )
    (net (code "69") (name "Net-(Q3-C)") (class "Default")
      (node (ref "D2") (pin "A") (pinfunction "A_A") (pintype "passive"))
      (node (ref "DC_RELAY") (pin "3") (pinfunction "3_3") (pintype "passive"))
      (node (ref "Q3") (pin "3") (pinfunction "C_3") (pintype "passive"))
    )
    (net (code "70") (name "Net-(R32-Pad2)") (class "Default")
      (node (ref "R32") (pin "2") (pinfunction "2_2") (pintype "passive"))
      (node (ref "R33") (pin "1") (pinfunction "1_1") (pintype "passive"))
    )
    (net (code "71") (name "Net-(R34-Pad2)") (class "Default")
      (node (ref "R34") (pin "2") (pinfunction "2_2") (pintype "passive"))
      (node (ref "R35") (pin "1") (pinfunction "1_1") (pintype "passive"))
    )
    (net (code "72") (name "Net-(R36-Pad2)") (class "Default")
      (node (ref "R36") (pin "2") (pinfunction "2_2") (pintype "passive"))
      (node (ref "R37") (pin "1") (pinfunction "1_1") (pintype "passive"))
    )
    (net (code "73") (name "Net-(R38-Pad2)") (class "Default")
      (node (ref "R38") (pin "2") (pinfunction "2_2") (pintype "passive"))
      (node (ref "R39") (pin "1") (pinfunction "1_1") (pintype "passive"))
    )
    (net (code "74") (name "Net-(U1-BST)") (class "Default")
      (node (ref "C32") (pin "1") (pinfunction "1_1") (pintype "passive"))
      (node (ref "U1") (pin "6") (pinfunction "BST_6") (pintype "bidirectional"))
    )
    (net (code "75") (name "PE") (class "Default")
      (node (ref "G1") (pin "1") (pinfunction "1_1") (pintype "passive"))
      (node (ref "IC8") (pin "P$2") (pinfunction "I1-_P$2") (pintype "bidirectional"))
      (node (ref "IC8") (pin "P$3") (pinfunction "I2-_P$3") (pintype "bidirectional"))
      (node (ref "M3") (pin "P$1") (pinfunction "1_P$1") (pintype "passive"))
      (node (ref "M4") (pin "P$1") (pinfunction "1_P$1") (pintype "passive"))
      (node (ref "U$3") (pin "P$1") (pinfunction "GND_P$1") (pintype "bidirectional"))
    )
    (net (code "76") (name "unconnected-(D1-AA-Pad3)") (class "Default")
      (node (ref "D1") (pin "3") (pinfunction "AA_3") (pintype "passive"))
    )
    (net (code "77") (name "unconnected-(D11-AA-Pad3)") (class "Default")
      (node (ref "D11") (pin "3") (pinfunction "AA_3") (pintype "passive"))
    )
    (net (code "78") (name "unconnected-(IC4-LV-Pad6)") (class "Default")
      (node (ref "IC4") (pin "6") (pinfunction "LV_6") (pintype "bidirectional"))
    )
    (net (code "79") (name "unconnected-(IC4-OSC-Pad7)") (class "Default")
      (node (ref "IC4") (pin "7") (pinfunction "OSC_7") (pintype "bidirectional"))
    )
    (net (code "80") (name "unconnected-(IC7-5-PadP$5)") (class "Default")
      (node (ref "IC7") (pin "P$5") (pinfunction "5_P$5") (pintype "bidirectional"))
    )
  )
)
